# 3_mcu.net
KiCad netlist of a schematic drawn in Altium Designer
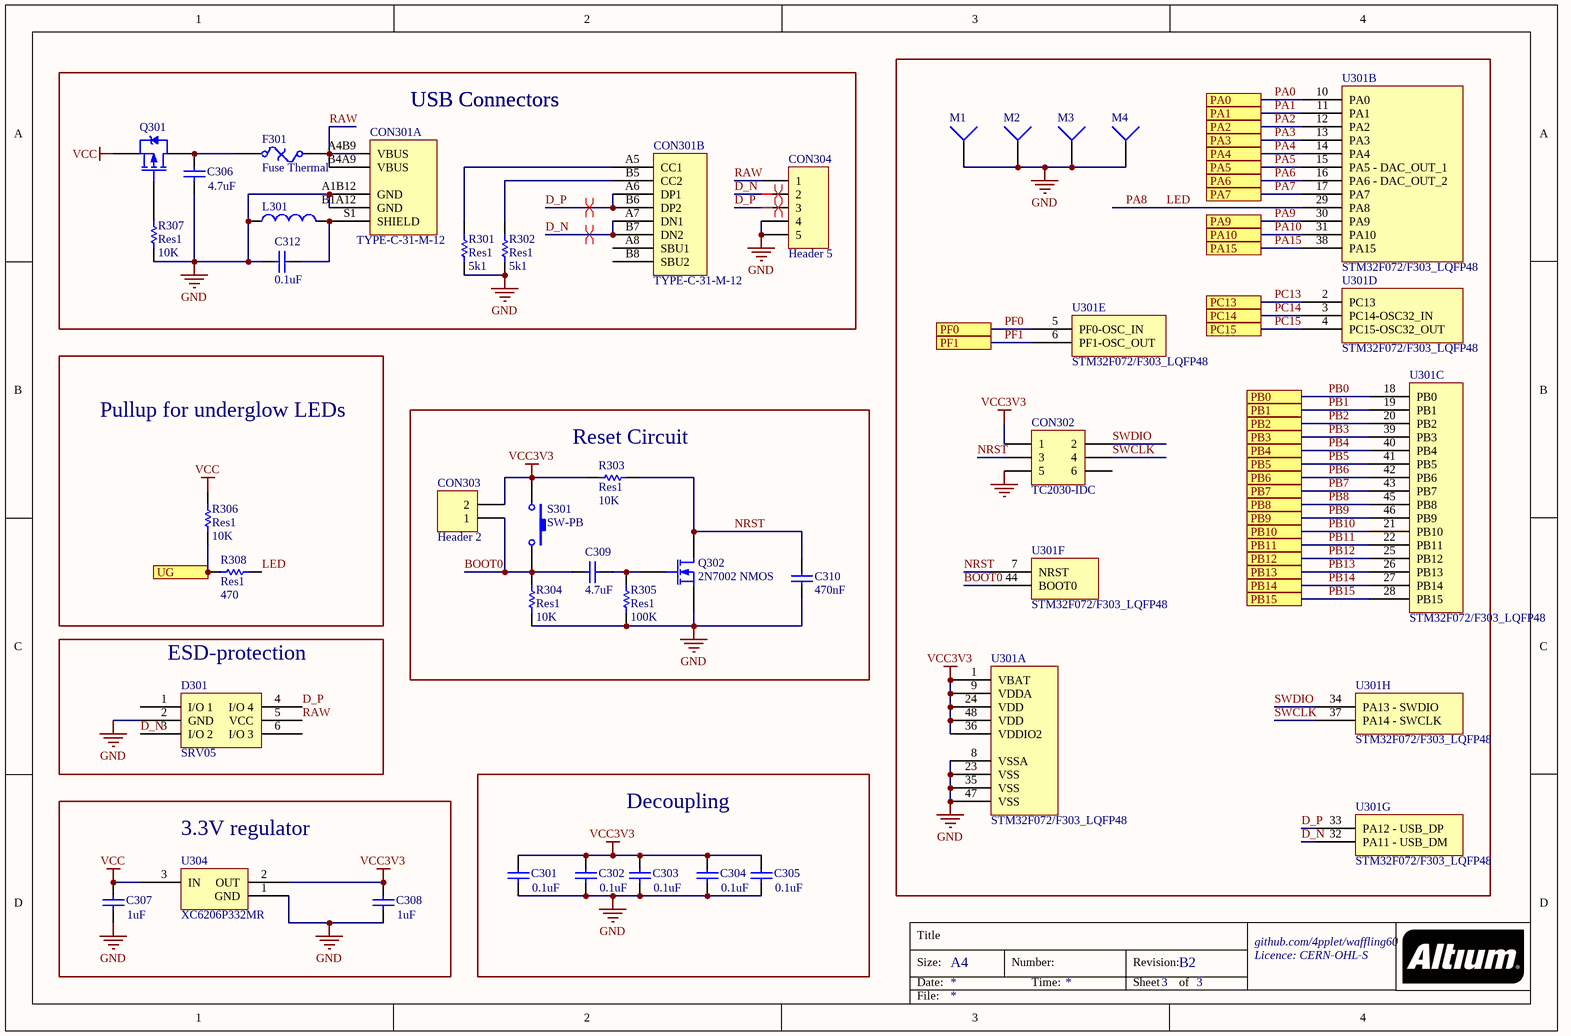
[diagram p0: 3_mcu.SchDoc]

(export (version "E")
  (design (tool "Eeschema 10.0.6"))
  (components
    (comp (ref "C301")
      (value "0.1uF")
      (footprint "C0603[1608]")
      (description "Capacitor")
      (fields (field (name "LCSC PART #") "C14663") (field (name "MRF.PART") "CC0603KRX7R9BB104"))
      (libsource (lib "Miscellaneous Devices") (part "Cap"))
    )
    (comp (ref "C302")
      (value "0.1uF")
      (footprint "C0603[1608]")
      (description "Capacitor")
      (fields (field (name "LCSC PART #") "C14663") (field (name "MRF.PART") "CC0603KRX7R9BB104"))
      (libsource (lib "Miscellaneous Devices") (part "Cap"))
    )
    (comp (ref "C303")
      (value "0.1uF")
      (footprint "C0603[1608]")
      (description "Capacitor")
      (fields (field (name "LCSC PART #") "C14663") (field (name "MRF.PART") "CC0603KRX7R9BB104"))
      (libsource (lib "Miscellaneous Devices") (part "Cap"))
    )
    (comp (ref "C304")
      (value "0.1uF")
      (footprint "C0603[1608]")
      (description "Capacitor")
      (fields (field (name "LCSC PART #") "C14663") (field (name "MRF.PART") "CC0603KRX7R9BB104"))
      (libsource (lib "Miscellaneous Devices") (part "Cap"))
    )
    (comp (ref "C305")
      (value "0.1uF")
      (footprint "C0603[1608]")
      (description "Capacitor")
      (fields (field (name "LCSC PART #") "C14663") (field (name "MRF.PART") "CC0603KRX7R9BB104"))
      (libsource (lib "Miscellaneous Devices") (part "Cap"))
    )
    (comp (ref "C306")
      (value "4.7uF")
      (footprint "C0603[1608]")
      (description "Capacitor")
      (fields (field (name "LCSC PART #") "C19666") (field (name "MRF.PART") "CL10A475KO8NNNC"))
      (libsource (lib "Miscellaneous Devices") (part "Cap"))
    )
    (comp (ref "C307")
      (value "1uF")
      (footprint "C0603[1608]")
      (description "Capacitor")
      (fields (field (name "LCSC PART #") "C15849") (field (name "MRF.PART") "CL10A105KB8NNNC"))
      (libsource (lib "Miscellaneous Devices") (part "Cap"))
    )
    (comp (ref "C308")
      (value "1uF")
      (footprint "C0603[1608]")
      (description "Capacitor")
      (fields (field (name "LCSC PART #") "C15849") (field (name "MRF.PART") "CL10A105KB8NNNC"))
      (libsource (lib "Miscellaneous Devices") (part "Cap"))
    )
    (comp (ref "C309")
      (value "4.7uF")
      (footprint "C0603[1608]")
      (description "Capacitor")
      (fields (field (name "LCSC PART #") "C19666") (field (name "MRF.PART") "CL10A475KO8NNNC"))
      (libsource (lib "Miscellaneous Devices") (part "Cap"))
    )
    (comp (ref "C310")
      (value "470nF")
      (footprint "C0603[1608]")
      (description "Capacitor")
      (fields (field (name "LCSC PART #") "C1623") (field (name "MRF.PART") "CL10B474KA8NNNC"))
      (libsource (lib "Miscellaneous Devices") (part "Cap"))
    )
    (comp (ref "C312")
      (value "0.1uF")
      (footprint "C0603[1608]")
      (description "Capacitor")
      (fields (field (name "LCSC PART #") "C14663") (field (name "MRF.PART") "CC0603KRX7R9BB104"))
      (libsource (lib "Miscellaneous Devices") (part "Cap"))
    )
    (comp (ref "CON301")
      (value "TYPE-C-31-M-12")
      (footprint "TYPE-C-31-M-12")
      (fields (field (name "LCSC PART #") "C165948"))
      (libsource (lib "Schlib1") (part "TYPE-C-31-M-12"))
    )
    (comp (ref "CON302")
      (value "TC2030-IDC")
      (footprint "TC2030-IDC-NL")
      (description "Header, 3-Pin, Dual row")
      (libsource (lib "Miscellaneous Connectors") (part "Header 3X2"))
    )
    (comp (ref "CON303")
      (value "Header 2")
      (footprint "HDR1X2")
      (description "Header, 2-Pin")
      (libsource (lib "Miscellaneous Connectors") (part "Header 2"))
    )
    (comp (ref "CON304")
      (value "Header 5")
      (footprint "UDB_combo_JST_MOLEX")
      (description "JST for USB daughter board")
      (fields (field (name "LCSC PART #") "C160404") (field (name "MRF.PART") "SM04B-SRSS-TB(LF)(SN)"))
      (libsource (lib "Miscellaneous Connectors") (part "Header 5"))
    )
    (comp (ref "D301")
      (value "SRV05")
      (footprint "SOT-23-6")
      (fields (field (name "LCSC PART #") "C85364") (field (name "MRF.PART") "SRV05-4-P-T7"))
      (libsource (lib "Keebs") (part "SRV05"))
    )
    (comp (ref "F301")
      (value "Fuse Thermal")
      (footprint "C1206[3216]")
      (description "Thermal Fuse")
      (fields (field (name "LCSC PART #") "C135338") (field (name "MRF.PART") "ASMD1206-050"))
      (libsource (lib "Miscellaneous Devices") (part "Fuse Thermal"))
    )
    (comp (ref "L301")
      (value "Inductor")
      (footprint "L0805")
      (fields (field (name "LCSC PART #") "C1015") (field (name "MRF.PART") "GZ2012D101TF"))
      (libsource (lib "Simulation Generic Components") (part "Inductor"))
    )
    (comp (ref "M1")
      (value "Socket")
      (footprint "mounting_hole")
      (libsource (lib "Miscellaneous Connectors") (part "Socket"))
    )
    (comp (ref "M2")
      (value "Socket")
      (footprint "mounting_hole")
      (libsource (lib "Miscellaneous Connectors") (part "Socket"))
    )
    (comp (ref "M3")
      (value "Socket")
      (footprint "mounting_hole")
      (libsource (lib "Miscellaneous Connectors") (part "Socket"))
    )
    (comp (ref "M4")
      (value "Socket")
      (footprint "mounting_hole")
      (libsource (lib "Miscellaneous Connectors") (part "Socket"))
    )
    (comp (ref "Q301")
      (value "PMOS-2")
      (footprint "SOT-23-3")
      (description "P-Channel Power MOSFET")
      (fields (field (name "LCSC PART #") "C10487") (field (name "MRF.PART") "SI2301CDS-T1-GE3"))
      (libsource (lib "Miscellaneous Devices") (part "PMOS-2"))
    )
    (comp (ref "Q302")
      (value "2N7002 NMOS")
      (footprint "SOT-23-3")
      (description "N-Channel MOSFET")
      (fields (field (name "LCSC PART #") "C8545") (field (name "MRF.PART") "2N7002"))
      (libsource (lib "Miscellaneous Devices") (part "MOSFET-N"))
    )
    (comp (ref "R301")
      (value "Res1")
      (footprint "R0603[1608]")
      (description "Resistor")
      (fields
        (field (name "ALTIUM_VALUE") "5k1")
        (field (name "LCSC PART #") "C23186")
        (field (name "MRF.PART") "0603WAF5101T5E")
      )
      (libsource (lib "Miscellaneous Devices") (part "Res1"))
    )
    (comp (ref "R302")
      (value "Res1")
      (footprint "R0603[1608]")
      (description "Resistor")
      (fields
        (field (name "ALTIUM_VALUE") "5k1")
        (field (name "LCSC PART #") "C23186")
        (field (name "MRF.PART") "0603WAF5101T5E")
      )
      (libsource (lib "Miscellaneous Devices") (part "Res1"))
    )
    (comp (ref "R303")
      (value "Res1")
      (footprint "R0603[1608]")
      (description "Resistor")
      (fields
        (field (name "ALTIUM_VALUE") "10K")
        (field (name "LCSC PART #") "C25804")
        (field (name "MRF.PART") "0603WAF1002T5E")
      )
      (libsource (lib "Miscellaneous Devices") (part "Res1"))
    )
    (comp (ref "R304")
      (value "Res1")
      (footprint "R0603[1608]")
      (description "Resistor")
      (fields
        (field (name "ALTIUM_VALUE") "10K")
        (field (name "LCSC PART #") "C25804")
        (field (name "MRF.PART") "0603WAF1002T5E")
      )
      (libsource (lib "Miscellaneous Devices") (part "Res1"))
    )
    (comp (ref "R305")
      (value "Res1")
      (footprint "R0603[1608]")
      (description "Resistor")
      (fields
        (field (name "ALTIUM_VALUE") "100K")
        (field (name "LCSC PART #") "C25803")
        (field (name "MRF.PART") "0603WAF1003T5E")
      )
      (libsource (lib "Miscellaneous Devices") (part "Res1"))
    )
    (comp (ref "R306")
      (value "Res1")
      (footprint "R0603[1608]")
      (description "Resistor")
      (fields
        (field (name "ALTIUM_VALUE") "10K")
        (field (name "LCSC PART #") "C25804")
        (field (name "MRF.PART") "0603WAF1002T5E")
      )
      (libsource (lib "Miscellaneous Devices") (part "Res1"))
    )
    (comp (ref "R307")
      (value "Res1")
      (footprint "R0603[1608]")
      (description "Resistor")
      (fields
        (field (name "ALTIUM_VALUE") "10K")
        (field (name "LCSC PART #") "C25804")
        (field (name "MRF.PART") "0603WAF1002T5E")
      )
      (libsource (lib "Miscellaneous Devices") (part "Res1"))
    )
    (comp (ref "R308")
      (value "Res1")
      (footprint "R0603[1608]")
      (description "Resistor")
      (fields
        (field (name "ALTIUM_VALUE") "470")
        (field (name "LCSC PART #") "C23179")
        (field (name "MRF.PART") "0603WAF4700T5E")
      )
      (libsource (lib "Miscellaneous Devices") (part "Res1"))
    )
    (comp (ref "S301")
      (value "SW-PB")
      (footprint "XKB Switch")
      (description "Switch")
      (fields (field (name "MRF.PART") "TS-1187A-C-D-B") (field (name "LCSC PART #") "C318888"))
      (libsource (lib "Miscellaneous Devices") (part "SW-PB"))
    )
    (comp (ref "U301")
      (value "STM32F072/F303_LQFP48")
      (footprint "STM32 - COMBO 7X7MM")
      (fields (field (name "LCSC PART #") "C915660") (field (name "MRF.PART") "APM32F072CBT6"))
      (libsource (lib "Keebs") (part "STM32F072/F303_LQFP48"))
    )
    (comp (ref "U304")
      (value "XC6206P332MR")
      (footprint "SOT-23-3")
      (fields (field (name "LCSC PART #") "C5446"))
      (libsource (lib "Keebs") (part "SOT23 LDO"))
    )
  )
  (nets
    (net (code "1") (name "/BOOT0") (class "Default")
      (node (ref "C309") (pin "1") (pinfunction "1_1") (pintype "passive"))
      (node (ref "CON303") (pin "1") (pinfunction "1_1") (pintype "passive"))
      (node (ref "R304") (pin "1") (pinfunction "1_1") (pintype "passive"))
      (node (ref "S301") (pin "2") (pinfunction "2_2") (pintype "passive"))
      (node (ref "U301") (pin "44") (pinfunction "BOOT0_44") (pintype "passive"))
    )
    (net (code "2") (name "/D_N") (class "Default")
      (node (ref "CON301") (pin "A7") (pinfunction "DN1_A7") (pintype "passive"))
      (node (ref "CON301") (pin "B7") (pinfunction "DN2_B7") (pintype "passive"))
      (node (ref "CON304") (pin "2") (pinfunction "2_2") (pintype "passive"))
      (node (ref "D301") (pin "3") (pinfunction "I/O_2_3") (pintype "passive"))
      (node (ref "U301") (pin "32") (pinfunction "PA11_-_USB_DM_32") (pintype "passive"))
    )
    (net (code "3") (name "/D_P") (class "Default")
      (node (ref "CON301") (pin "A6") (pinfunction "DP1_A6") (pintype "passive"))
      (node (ref "CON301") (pin "B6") (pinfunction "DP2_B6") (pintype "passive"))
      (node (ref "CON304") (pin "3") (pinfunction "3_3") (pintype "passive"))
      (node (ref "D301") (pin "4") (pinfunction "I/O_4_4") (pintype "passive"))
      (node (ref "U301") (pin "33") (pinfunction "PA12_-_USB_DP_33") (pintype "passive"))
    )
    (net (code "4") (name "/LED") (class "Default")
      (node (ref "R308") (pin "2") (pinfunction "2_2") (pintype "passive"))
      (node (ref "U301") (pin "29") (pinfunction "PA8_29") (pintype "passive"))
    )
    (net (code "5") (name "/NRST") (class "Default")
      (node (ref "C310") (pin "1") (pinfunction "1_1") (pintype "passive"))
      (node (ref "CON302") (pin "3") (pinfunction "3_3") (pintype "passive"))
      (node (ref "Q302") (pin "3") (pinfunction "D_3") (pintype "passive"))
      (node (ref "R303") (pin "2") (pinfunction "2_2") (pintype "passive"))
      (node (ref "U301") (pin "7") (pinfunction "NRST_7") (pintype "passive"))
    )
    (net (code "6") (name "/PA0") (class "Default")
      (node (ref "U301") (pin "10") (pinfunction "PA0_10") (pintype "passive"))
    )
    (net (code "7") (name "/PA1") (class "Default")
      (node (ref "U301") (pin "11") (pinfunction "PA1_11") (pintype "passive"))
    )
    (net (code "8") (name "/PA2") (class "Default")
      (node (ref "U301") (pin "12") (pinfunction "PA2_12") (pintype "passive"))
    )
    (net (code "9") (name "/PA3") (class "Default")
      (node (ref "U301") (pin "13") (pinfunction "PA3_13") (pintype "passive"))
    )
    (net (code "10") (name "/PA4") (class "Default")
      (node (ref "U301") (pin "14") (pinfunction "PA4_14") (pintype "passive"))
    )
    (net (code "11") (name "/PA5") (class "Default")
      (node (ref "U301") (pin "15") (pinfunction "PA5_-_DAC_OUT_1_15") (pintype "passive"))
    )
    (net (code "12") (name "/PA6") (class "Default")
      (node (ref "U301") (pin "16") (pinfunction "PA6_-_DAC_OUT_2_16") (pintype "passive"))
    )
    (net (code "13") (name "/PA7") (class "Default")
      (node (ref "U301") (pin "17") (pinfunction "PA7_17") (pintype "passive"))
    )
    (net (code "14") (name "/PA9") (class "Default")
      (node (ref "U301") (pin "30") (pinfunction "PA9_30") (pintype "passive"))
    )
    (net (code "15") (name "/PA10") (class "Default")
      (node (ref "U301") (pin "31") (pinfunction "PA10_31") (pintype "passive"))
    )
    (net (code "16") (name "/PA15") (class "Default")
      (node (ref "U301") (pin "38") (pinfunction "PA15_38") (pintype "passive"))
    )
    (net (code "17") (name "/PB0") (class "Default")
      (node (ref "U301") (pin "18") (pinfunction "PB0_18") (pintype "passive"))
    )
    (net (code "18") (name "/PB1") (class "Default")
      (node (ref "U301") (pin "19") (pinfunction "PB1_19") (pintype "passive"))
    )
    (net (code "19") (name "/PB2") (class "Default")
      (node (ref "U301") (pin "20") (pinfunction "PB2_20") (pintype "passive"))
    )
    (net (code "20") (name "/PB3") (class "Default")
      (node (ref "U301") (pin "39") (pinfunction "PB3_39") (pintype "passive"))
    )
    (net (code "21") (name "/PB4") (class "Default")
      (node (ref "U301") (pin "40") (pinfunction "PB4_40") (pintype "passive"))
    )
    (net (code "22") (name "/PB5") (class "Default")
      (node (ref "U301") (pin "41") (pinfunction "PB5_41") (pintype "passive"))
    )
    (net (code "23") (name "/PB6") (class "Default")
      (node (ref "U301") (pin "42") (pinfunction "PB6_42") (pintype "passive"))
    )
    (net (code "24") (name "/PB7") (class "Default")
      (node (ref "U301") (pin "43") (pinfunction "PB7_43") (pintype "passive"))
    )
    (net (code "25") (name "/PB8") (class "Default")
      (node (ref "U301") (pin "45") (pinfunction "PB8_45") (pintype "passive"))
    )
    (net (code "26") (name "/PB9") (class "Default")
      (node (ref "U301") (pin "46") (pinfunction "PB9_46") (pintype "passive"))
    )
    (net (code "27") (name "/PB10") (class "Default")
      (node (ref "U301") (pin "21") (pinfunction "PB10_21") (pintype "passive"))
    )
    (net (code "28") (name "/PB11") (class "Default")
      (node (ref "U301") (pin "22") (pinfunction "PB11_22") (pintype "passive"))
    )
    (net (code "29") (name "/PB12") (class "Default")
      (node (ref "U301") (pin "25") (pinfunction "PB12_25") (pintype "passive"))
    )
    (net (code "30") (name "/PB13") (class "Default")
      (node (ref "U301") (pin "26") (pinfunction "PB13_26") (pintype "passive"))
    )
    (net (code "31") (name "/PB14") (class "Default")
      (node (ref "U301") (pin "27") (pinfunction "PB14_27") (pintype "passive"))
    )
    (net (code "32") (name "/PB15") (class "Default")
      (node (ref "U301") (pin "28") (pinfunction "PB15_28") (pintype "passive"))
    )
    (net (code "33") (name "/PC13") (class "Default")
      (node (ref "U301") (pin "2") (pinfunction "PC13_2") (pintype "passive"))
    )
    (net (code "34") (name "/PC14") (class "Default")
      (node (ref "U301") (pin "3") (pinfunction "PC14-OSC32_IN_3") (pintype "passive"))
    )
    (net (code "35") (name "/PC15") (class "Default")
      (node (ref "U301") (pin "4") (pinfunction "PC15-OSC32_OUT_4") (pintype "passive"))
    )
    (net (code "36") (name "/PF0") (class "Default")
      (node (ref "U301") (pin "5") (pinfunction "PF0-OSC_IN_5") (pintype "passive"))
    )
    (net (code "37") (name "/PF1") (class "Default")
      (node (ref "U301") (pin "6") (pinfunction "PF1-OSC_OUT_6") (pintype "passive"))
    )
    (net (code "38") (name "/RAW") (class "Default")
      (node (ref "CON301") (pin "A4B9") (pinfunction "VBUS_A4B9") (pintype "passive"))
      (node (ref "CON301") (pin "B4A9") (pinfunction "VBUS_B4A9") (pintype "passive"))
      (node (ref "CON304") (pin "1") (pinfunction "1_1") (pintype "passive"))
      (node (ref "D301") (pin "5") (pinfunction "VCC_5") (pintype "passive"))
      (node (ref "F301") (pin "2") (pinfunction "2_2") (pintype "passive"))
    )
    (net (code "39") (name "/SWCLK") (class "Default")
      (node (ref "CON302") (pin "4") (pinfunction "4_4") (pintype "passive"))
      (node (ref "U301") (pin "37") (pinfunction "PA14_-_SWCLK_37") (pintype "passive"))
    )
    (net (code "40") (name "/SWDIO") (class "Default")
      (node (ref "CON302") (pin "2") (pinfunction "2_2") (pintype "passive"))
      (node (ref "U301") (pin "34") (pinfunction "PA13_-_SWDIO_34") (pintype "passive"))
    )
    (net (code "41") (name "/UG") (class "Default")
      (node (ref "R306") (pin "2") (pinfunction "2_2") (pintype "passive"))
      (node (ref "R308") (pin "1") (pinfunction "1_1") (pintype "passive"))
    )
    (net (code "42") (name "GND") (class "Default")
      (node (ref "C301") (pin "1") (pinfunction "1_1") (pintype "passive"))
      (node (ref "C302") (pin "1") (pinfunction "1_1") (pintype "passive"))
      (node (ref "C303") (pin "1") (pinfunction "1_1") (pintype "passive"))
      (node (ref "C304") (pin "1") (pinfunction "1_1") (pintype "passive"))
      (node (ref "C305") (pin "1") (pinfunction "1_1") (pintype "passive"))
      (node (ref "C306") (pin "1") (pinfunction "1_1") (pintype "passive"))
      (node (ref "C307") (pin "1") (pinfunction "1_1") (pintype "passive"))
      (node (ref "C308") (pin "1") (pinfunction "1_1") (pintype "passive"))
      (node (ref "C310") (pin "2") (pinfunction "2_2") (pintype "passive"))
      (node (ref "C312") (pin "1") (pinfunction "1_1") (pintype "passive"))
      (node (ref "CON301") (pin "A1B12") (pinfunction "GND_A1B12") (pintype "passive"))
      (node (ref "CON301") (pin "B1A12") (pinfunction "GND_B1A12") (pintype "passive"))
      (node (ref "CON302") (pin "5") (pinfunction "5_5") (pintype "passive"))
      (node (ref "CON304") (pin "4") (pinfunction "4_4") (pintype "passive"))
      (node (ref "CON304") (pin "5") (pinfunction "5_5") (pintype "passive"))
      (node (ref "D301") (pin "2") (pinfunction "GND_2") (pintype "passive"))
      (node (ref "L301") (pin "1") (pinfunction "1_1") (pintype "passive"))
      (node (ref "M1") (pin "1") (pinfunction "1_1") (pintype "passive"))
      (node (ref "M2") (pin "1") (pinfunction "1_1") (pintype "passive"))
      (node (ref "M3") (pin "1") (pinfunction "1_1") (pintype "passive"))
      (node (ref "M4") (pin "1") (pinfunction "1_1") (pintype "passive"))
      (node (ref "Q302") (pin "2") (pinfunction "S_2") (pintype "passive"))
      (node (ref "R301") (pin "2") (pinfunction "2_2") (pintype "passive"))
      (node (ref "R302") (pin "2") (pinfunction "2_2") (pintype "passive"))
      (node (ref "R304") (pin "2") (pinfunction "2_2") (pintype "passive"))
      (node (ref "R305") (pin "2") (pinfunction "2_2") (pintype "passive"))
      (node (ref "R307") (pin "2") (pinfunction "2_2") (pintype "passive"))
      (node (ref "U301") (pin "23") (pinfunction "VSS_23") (pintype "passive"))
      (node (ref "U301") (pin "35") (pinfunction "VSS_35") (pintype "passive"))
      (node (ref "U301") (pin "47") (pinfunction "VSS_47") (pintype "passive"))
      (node (ref "U301") (pin "8") (pinfunction "VSSA_8") (pintype "passive"))
      (node (ref "U304") (pin "1") (pinfunction "GND_1") (pintype "passive"))
    )
    (net (code "43") (name "Net-(CON301A-SHIELD)") (class "Default")
      (node (ref "C312") (pin "2") (pinfunction "2_2") (pintype "passive"))
      (node (ref "CON301") (pin "S1") (pinfunction "SHIELD_S1") (pintype "passive"))
      (node (ref "L301") (pin "2") (pinfunction "2_2") (pintype "passive"))
    )
    (net (code "44") (name "Net-(CON301B-CC1)") (class "Default")
      (node (ref "CON301") (pin "A5") (pinfunction "CC1_A5") (pintype "passive"))
      (node (ref "R301") (pin "1") (pinfunction "1_1") (pintype "passive"))
    )
    (net (code "45") (name "Net-(CON301B-CC2)") (class "Default")
      (node (ref "CON301") (pin "B5") (pinfunction "CC2_B5") (pintype "passive"))
      (node (ref "R302") (pin "1") (pinfunction "1_1") (pintype "passive"))
    )
    (net (code "46") (name "Net-(Q301-D)") (class "Default")
      (node (ref "C306") (pin "2") (pinfunction "2_2") (pintype "passive"))
      (node (ref "F301") (pin "1") (pinfunction "1_1") (pintype "passive"))
      (node (ref "Q301") (pin "3") (pinfunction "D_3") (pintype "passive"))
    )
    (net (code "47") (name "Net-(Q301-G)") (class "Default")
      (node (ref "Q301") (pin "1") (pinfunction "G_1") (pintype "passive"))
      (node (ref "R307") (pin "1") (pinfunction "1_1") (pintype "passive"))
    )
    (net (code "48") (name "Net-(Q302-G)") (class "Default")
      (node (ref "C309") (pin "2") (pinfunction "2_2") (pintype "passive"))
      (node (ref "Q302") (pin "1") (pinfunction "G_1") (pintype "passive"))
      (node (ref "R305") (pin "1") (pinfunction "1_1") (pintype "passive"))
    )
    (net (code "49") (name "VCC") (class "Default")
      (node (ref "C307") (pin "2") (pinfunction "2_2") (pintype "passive"))
      (node (ref "Q301") (pin "2") (pinfunction "S_2") (pintype "passive"))
      (node (ref "R306") (pin "1") (pinfunction "1_1") (pintype "passive"))
      (node (ref "U304") (pin "3") (pinfunction "IN_3") (pintype "passive"))
    )
    (net (code "50") (name "VCC3V3") (class "Default")
      (node (ref "C301") (pin "2") (pinfunction "2_2") (pintype "passive"))
      (node (ref "C302") (pin "2") (pinfunction "2_2") (pintype "passive"))
      (node (ref "C303") (pin "2") (pinfunction "2_2") (pintype "passive"))
      (node (ref "C304") (pin "2") (pinfunction "2_2") (pintype "passive"))
      (node (ref "C305") (pin "2") (pinfunction "2_2") (pintype "passive"))
      (node (ref "C308") (pin "2") (pinfunction "2_2") (pintype "passive"))
      (node (ref "CON302") (pin "1") (pinfunction "1_1") (pintype "passive"))
      (node (ref "CON303") (pin "2") (pinfunction "2_2") (pintype "passive"))
      (node (ref "R303") (pin "1") (pinfunction "1_1") (pintype "passive"))
      (node (ref "S301") (pin "1") (pinfunction "1_1") (pintype "passive"))
      (node (ref "U301") (pin "1") (pinfunction "VBAT_1") (pintype "passive"))
      (node (ref "U301") (pin "24") (pinfunction "VDD_24") (pintype "passive"))
      (node (ref "U301") (pin "36") (pinfunction "VDDIO2_36") (pintype "passive"))
      (node (ref "U301") (pin "48") (pinfunction "VDD_48") (pintype "passive"))
      (node (ref "U301") (pin "9") (pinfunction "VDDA_9") (pintype "passive"))
      (node (ref "U304") (pin "2") (pinfunction "OUT_2") (pintype "passive"))
    )
    (net (code "51") (name "unconnected-(CON301B-SBU1-PadA8)") (class "Default")
      (node (ref "CON301") (pin "A8") (pinfunction "SBU1_A8") (pintype "passive"))
    )
    (net (code "52") (name "unconnected-(CON301B-SBU2-PadB8)") (class "Default")
      (node (ref "CON301") (pin "B8") (pinfunction "SBU2_B8") (pintype "passive"))
    )
    (net (code "53") (name "unconnected-(CON302-Pad6)") (class "Default")
      (node (ref "CON302") (pin "6") (pinfunction "6_6") (pintype "passive"))
    )
    (net (code "54") (name "unconnected-(D301-I{slash}O_1-Pad1)") (class "Default")
      (node (ref "D301") (pin "1") (pinfunction "I/O_1_1") (pintype "passive"))
    )
    (net (code "55") (name "unconnected-(D301-I{slash}O_3-Pad6)") (class "Default")
      (node (ref "D301") (pin "6") (pinfunction "I/O_3_6") (pintype "passive"))
    )
  )
)
